# TSL1401CS_SensorBoard.net
KiCad netlist of a schematic drawn in Altium Designer
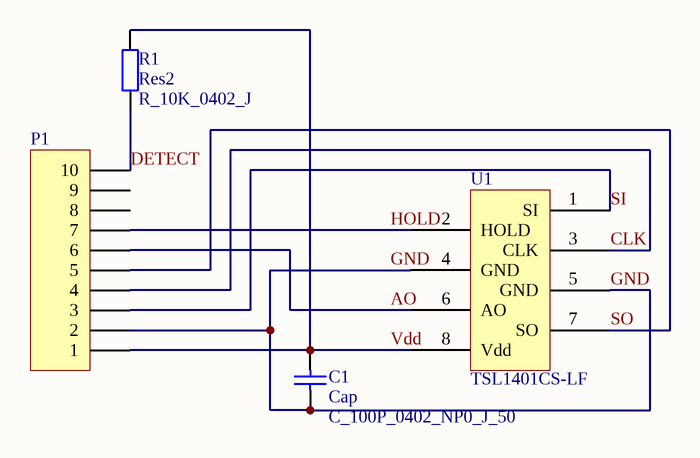
[diagram p0: TSL1401CS_SensorBoard.SchDoc]

(export (version "E")
  (design (tool "Eeschema 10.0.6"))
  (components
    (comp (ref "C1")
      (value "Cap")
      (footprint "C_0402")
      (description "Capacitor")
      (fields
        (field (name "ALTIUM_VALUE") "C_100P_0402_NP0_J_50")
        (field (name "PUBLISHER") "Altium Limited")
      )
      (libsource (lib "Miscellaneous Devices") (part "Cap"))
    )
    (comp (ref "P1")
      (value "Header 10")
      (footprint "609-4377-ND")
      (description "Header, 10-Pin")
      (fields (field (name "PUBLISHER") "Altium Limited"))
      (libsource (lib "Miscellaneous Connectors") (part "Header 10"))
    )
    (comp (ref "R1")
      (value "Res2")
      (footprint "R_0402")
      (description "Resistor")
      (fields (field (name "ALTIUM_VALUE") "R_10K_0402_J") (field (name "PUBLISHER") "Altium Limited"))
      (libsource (lib "Miscellaneous Devices") (part "Res2"))
    )
    (comp (ref "U1")
      (value "TSL1401CS-LF")
      (footprint "TSL1401CS-LF solder bump linear array")
      (libsource (lib "BrewBit") (part "TSL1401CS-LF"))
    )
  )
  (nets
    (net (code "1") (name "/AO") (class "Default")
      (node (ref "P1") (pin "6") (pinfunction "6_6") (pintype "passive"))
      (node (ref "U1") (pin "6") (pinfunction "AO_6") (pintype "passive"))
    )
    (net (code "2") (name "/CLK") (class "Default")
      (node (ref "P1") (pin "4") (pinfunction "4_4") (pintype "passive"))
      (node (ref "U1") (pin "3") (pinfunction "CLK_3") (pintype "passive"))
    )
    (net (code "3") (name "/DETECT") (class "Default")
      (node (ref "P1") (pin "10") (pinfunction "10_10") (pintype "passive"))
      (node (ref "R1") (pin "1") (pinfunction "1_1") (pintype "passive"))
    )
    (net (code "4") (name "/GND") (class "Default")
      (node (ref "C1") (pin "1") (pinfunction "Vdd_1") (pintype "passive"))
      (node (ref "P1") (pin "2") (pinfunction "2_2") (pintype "passive"))
      (node (ref "U1") (pin "4") (pinfunction "GND_4") (pintype "passive"))
      (node (ref "U1") (pin "5") (pinfunction "GND_5") (pintype "passive"))
    )
    (net (code "5") (name "/HOLD") (class "Default")
      (node (ref "P1") (pin "7") (pinfunction "7_7") (pintype "passive"))
      (node (ref "U1") (pin "2") (pinfunction "HOLD_2") (pintype "passive"))
    )
    (net (code "6") (name "/SI") (class "Default")
      (node (ref "P1") (pin "3") (pinfunction "3_3") (pintype "passive"))
      (node (ref "U1") (pin "1") (pinfunction "SI_1") (pintype "passive"))
    )
    (net (code "7") (name "/SO") (class "Default")
      (node (ref "P1") (pin "5") (pinfunction "5_5") (pintype "passive"))
      (node (ref "U1") (pin "7") (pinfunction "SO_7") (pintype "passive"))
    )
    (net (code "8") (name "/Vdd") (class "Default")
      (node (ref "C1") (pin "2") (pinfunction "GND_2") (pintype "passive"))
      (node (ref "P1") (pin "1") (pinfunction "1_1") (pintype "passive"))
      (node (ref "R1") (pin "2") (pinfunction "2_2") (pintype "passive"))
      (node (ref "U1") (pin "8") (pinfunction "Vdd_8") (pintype "passive"))
    )
    (net (code "9") (name "unconnected-(P1-Pad8)") (class "Default")
      (node (ref "P1") (pin "8") (pinfunction "8_8") (pintype "passive"))
    )
    (net (code "10") (name "unconnected-(P1-Pad9)") (class "Default")
      (node (ref "P1") (pin "9") (pinfunction "9_9") (pintype "passive"))
    )
  )
)
